# ican.net
KiCad netlist of a schematic drawn in EAGLE
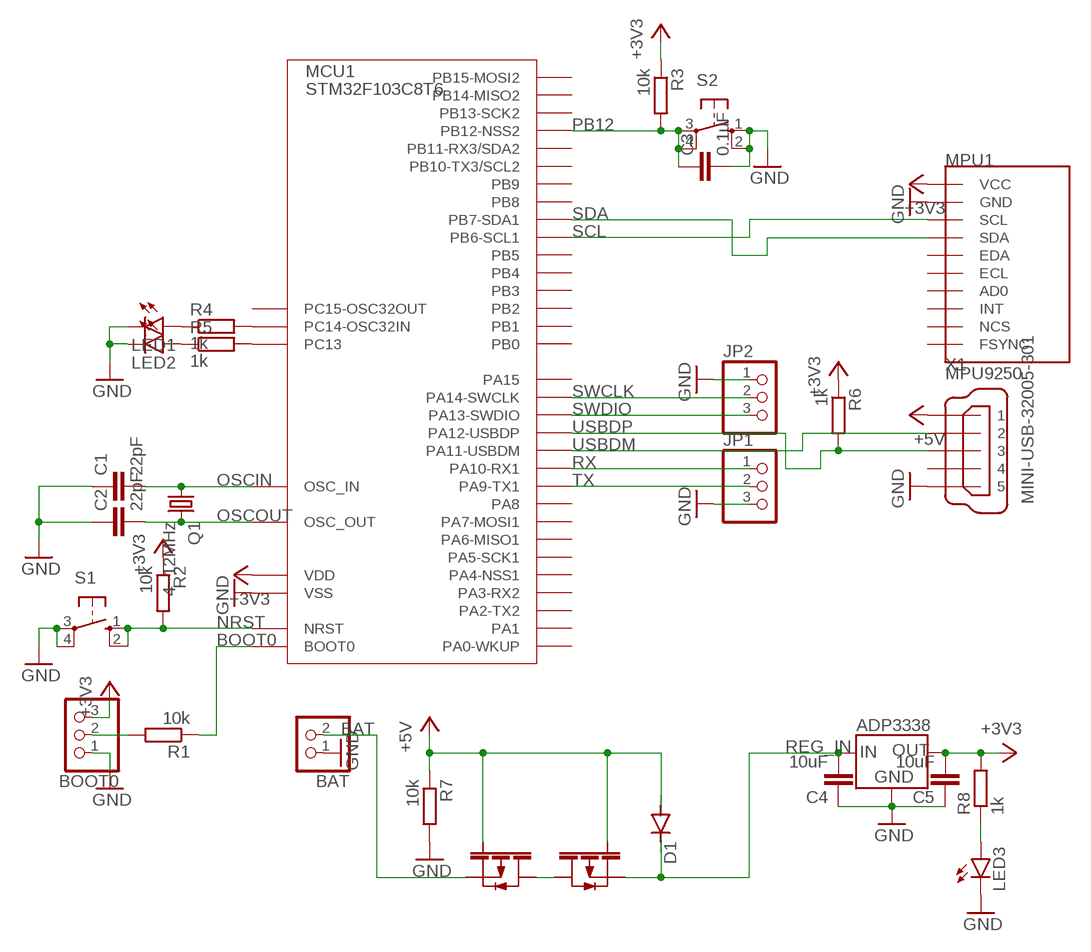
[diagram p0: schematic, sheet 1]

(export (version "E")
  (design (tool "Eeschema 10.0.6"))
  (components
    (comp (ref "BAT")
      (value "PINHD-1X2")
      (footprint "eagle-import:1X02")
      (libsource (lib "eagle-import") (part "PINHD-1X2"))
    )
    (comp (ref "BOOT0")
      (value "PINHD-1X3")
      (footprint "eagle-import:1X03")
      (libsource (lib "eagle-import") (part "PINHD-1X3"))
    )
    (comp (ref "C1")
      (value "22pF")
      (footprint "eagle-import:C2012")
      (libsource (lib "eagle-import") (part "C-EUC2012"))
    )
    (comp (ref "C2")
      (value "22pF")
      (footprint "eagle-import:C2012")
      (libsource (lib "eagle-import") (part "C-EUC2012"))
    )
    (comp (ref "C3")
      (value "0.1uF")
      (footprint "eagle-import:C2012")
      (libsource (lib "eagle-import") (part "C-EUC2012"))
    )
    (comp (ref "C4")
      (value "10uF")
      (footprint "eagle-import:C2012")
      (libsource (lib "eagle-import") (part "C-EUC2012"))
    )
    (comp (ref "C5")
      (value "10uF")
      (footprint "eagle-import:C2012")
      (libsource (lib "eagle-import") (part "C-EUC2012"))
    )
    (comp (ref "D1")
      (value "DIODE-SOD123")
      (footprint "eagle-import:SOD123")
      (libsource (lib "eagle-import") (part "DIODE-SOD123"))
    )
    (comp (ref "FET1")
      (value "PCH")
      (footprint "eagle-import:SOT-23")
      (libsource (lib "eagle-import") (part "PCH"))
    )
    (comp (ref "FET2")
      (value "PCH")
      (footprint "eagle-import:SOT-23")
      (libsource (lib "eagle-import") (part "PCH"))
    )
    (comp (ref "IC1")
      (value "ADP3338-3.3")
      (footprint "eagle-import:SOT-223")
      (libsource (lib "eagle-import") (part "ADP3338-3.3"))
    )
    (comp (ref "JP1")
      (value "PINHD-1X3")
      (footprint "eagle-import:1X03")
      (libsource (lib "eagle-import") (part "PINHD-1X3"))
    )
    (comp (ref "JP2")
      (value "PINHD-1X3")
      (footprint "eagle-import:1X03")
      (libsource (lib "eagle-import") (part "PINHD-1X3"))
    )
    (comp (ref "LED1")
      (value "LEDCHIPLED_1206")
      (footprint "eagle-import:CHIPLED_1206")
      (libsource (lib "eagle-import") (part "LEDCHIPLED_1206"))
    )
    (comp (ref "LED2")
      (value "LEDCHIPLED_1206")
      (footprint "eagle-import:CHIPLED_1206")
      (libsource (lib "eagle-import") (part "LEDCHIPLED_1206"))
    )
    (comp (ref "LED3")
      (value "LEDCHIPLED_1206")
      (footprint "eagle-import:CHIPLED_1206")
      (libsource (lib "eagle-import") (part "LEDCHIPLED_1206"))
    )
    (comp (ref "MCU1")
      (value "STM32F103C8T6")
      (footprint "eagle-import:LQFP48")
      (libsource (lib "eagle-import") (part "STM32F103C8T6"))
    )
    (comp (ref "MPU1")
      (value "MPU9250")
      (footprint "eagle-import:GY-9250")
      (libsource (lib "eagle-import") (part "MPU9250"))
    )
    (comp (ref "Q1")
      (value "4~12MHz")
      (footprint "eagle-import:HC49_S")
      (libsource (lib "eagle-import") (part "CRYSTALHC49S"))
    )
    (comp (ref "R1")
      (value "10k")
      (footprint "eagle-import:R2012")
      (libsource (lib "eagle-import") (part "R-EU_R2012"))
    )
    (comp (ref "R2")
      (value "10k")
      (footprint "eagle-import:R2012")
      (libsource (lib "eagle-import") (part "R-EU_R2012"))
    )
    (comp (ref "R3")
      (value "10k")
      (footprint "eagle-import:R2012")
      (libsource (lib "eagle-import") (part "R-EU_R2012"))
    )
    (comp (ref "R4")
      (value "1k")
      (footprint "eagle-import:R2012")
      (libsource (lib "eagle-import") (part "R-EU_R2012"))
    )
    (comp (ref "R5")
      (value "1k")
      (footprint "eagle-import:R2012")
      (libsource (lib "eagle-import") (part "R-EU_R2012"))
    )
    (comp (ref "R6")
      (value "1k")
      (footprint "eagle-import:R2012")
      (libsource (lib "eagle-import") (part "R-EU_R2012"))
    )
    (comp (ref "R7")
      (value "10k")
      (footprint "eagle-import:R2012")
      (libsource (lib "eagle-import") (part "R-EU_R2012"))
    )
    (comp (ref "R8")
      (value "1k")
      (footprint "eagle-import:R2012")
      (libsource (lib "eagle-import") (part "R-EU_R2012"))
    )
    (comp (ref "S1")
      (value "10-XX")
      (footprint "eagle-import:B3F-10XX")
      (fields (field (name "MPN") "B3F-1000"))
      (libsource (lib "eagle-import") (part "10-XX"))
    )
    (comp (ref "S2")
      (value "10-XX")
      (footprint "eagle-import:B3F-10XX")
      (fields (field (name "MPN") "B3F-1000"))
      (libsource (lib "eagle-import") (part "10-XX"))
    )
    (comp (ref "X1")
      (value "MINI-USB-32005-301")
      (footprint "eagle-import:32005-301")
      (libsource (lib "eagle-import") (part "MINI-USB-32005-301"))
    )
  )
  (nets
    (net (code "1") (name "+3V3") (class "Default")
      (node (ref "BOOT0") (pin "3") (pinfunction "3_3") (pintype "passive"))
      (node (ref "C5") (pin "2") (pinfunction "2_2") (pintype "passive"))
      (node (ref "IC1") (pin "1") (pinfunction "OUT_1") (pintype "output"))
      (node (ref "IC1") (pin "2") (pinfunction "OUT_2") (pintype "output"))
      (node (ref "MCU1") (pin "1") (pinfunction "VDD_1") (pintype "bidirectional"))
      (node (ref "MCU1") (pin "24") (pinfunction "VDD_24") (pintype "bidirectional"))
      (node (ref "MCU1") (pin "36") (pinfunction "VDD_36") (pintype "bidirectional"))
      (node (ref "MCU1") (pin "48") (pinfunction "VDD_48") (pintype "bidirectional"))
      (node (ref "MCU1") (pin "9") (pinfunction "VDD_9") (pintype "bidirectional"))
      (node (ref "MPU1") (pin "P1") (pinfunction "VCC_P1") (pintype "bidirectional"))
      (node (ref "R2") (pin "1") (pinfunction "1_1") (pintype "passive"))
      (node (ref "R3") (pin "1") (pinfunction "1_1") (pintype "passive"))
      (node (ref "R6") (pin "1") (pinfunction "1_1") (pintype "passive"))
      (node (ref "R8") (pin "2") (pinfunction "2_2") (pintype "passive"))
    )
    (net (code "2") (name "+5V") (class "Default")
      (node (ref "D1") (pin "A") (pinfunction "A_A") (pintype "passive"))
      (node (ref "FET1") (pin "P$1") (pinfunction "P$1_P$1") (pintype "bidirectional"))
      (node (ref "FET2") (pin "P$1") (pinfunction "P$1_P$1") (pintype "bidirectional"))
      (node (ref "R7") (pin "1") (pinfunction "1_1") (pintype "passive"))
      (node (ref "X1") (pin "1") (pinfunction "1_1") (pintype "passive"))
    )
    (net (code "3") (name "/BAT") (class "Default")
      (node (ref "BAT") (pin "2") (pinfunction "2_2") (pintype "passive"))
      (node (ref "FET1") (pin "P$2") (pinfunction "P$2_P$2") (pintype "bidirectional"))
    )
    (net (code "4") (name "/BOOT0") (class "Default")
      (node (ref "MCU1") (pin "44") (pinfunction "BOOT0_44") (pintype "bidirectional"))
      (node (ref "R1") (pin "1") (pinfunction "1_1") (pintype "passive"))
    )
    (net (code "5") (name "/NRST") (class "Default")
      (node (ref "MCU1") (pin "7") (pinfunction "NRST_7") (pintype "bidirectional"))
      (node (ref "R2") (pin "2") (pinfunction "2_2") (pintype "passive"))
      (node (ref "S1") (pin "1") (pinfunction "S_1") (pintype "passive"))
      (node (ref "S1") (pin "2") (pinfunction "S1_2") (pintype "passive"))
    )
    (net (code "6") (name "/OSCIN") (class "Default")
      (node (ref "C1") (pin "2") (pinfunction "2_2") (pintype "passive"))
      (node (ref "MCU1") (pin "5") (pinfunction "OSC_IN_5") (pintype "bidirectional"))
      (node (ref "Q1") (pin "1") (pinfunction "1_1") (pintype "passive"))
    )
    (net (code "7") (name "/OSCOUT") (class "Default")
      (node (ref "C2") (pin "2") (pinfunction "2_2") (pintype "passive"))
      (node (ref "MCU1") (pin "6") (pinfunction "OSC_OUT_6") (pintype "bidirectional"))
      (node (ref "Q1") (pin "2") (pinfunction "2_2") (pintype "passive"))
    )
    (net (code "8") (name "/PB12") (class "Default")
      (node (ref "C3") (pin "1") (pinfunction "1_1") (pintype "passive"))
      (node (ref "MCU1") (pin "25") (pinfunction "PB12-NSS2_25") (pintype "bidirectional"))
      (node (ref "R3") (pin "2") (pinfunction "2_2") (pintype "passive"))
      (node (ref "S2") (pin "3") (pinfunction "P_3") (pintype "passive"))
      (node (ref "S2") (pin "4") (pinfunction "P1_4") (pintype "passive"))
    )
    (net (code "9") (name "/REG_IN") (class "Default")
      (node (ref "C4") (pin "2") (pinfunction "2_2") (pintype "passive"))
      (node (ref "D1") (pin "C") (pinfunction "C_C") (pintype "passive"))
      (node (ref "FET2") (pin "P$2") (pinfunction "P$2_P$2") (pintype "bidirectional"))
      (node (ref "IC1") (pin "3") (pinfunction "IN_3") (pintype "input"))
    )
    (net (code "10") (name "/RX") (class "Default")
      (node (ref "JP1") (pin "1") (pinfunction "1_1") (pintype "passive"))
      (node (ref "MCU1") (pin "31") (pinfunction "PA10-RX1_31") (pintype "bidirectional"))
    )
    (net (code "11") (name "/SCL") (class "Default")
      (node (ref "MCU1") (pin "42") (pinfunction "PB6-SCL1_42") (pintype "bidirectional"))
      (node (ref "MPU1") (pin "P3") (pinfunction "SCL_P3") (pintype "bidirectional"))
    )
    (net (code "12") (name "/SDA") (class "Default")
      (node (ref "MCU1") (pin "43") (pinfunction "PB7-SDA1_43") (pintype "bidirectional"))
      (node (ref "MPU1") (pin "P4") (pinfunction "SDA_P4") (pintype "bidirectional"))
    )
    (net (code "13") (name "/SWCLK") (class "Default")
      (node (ref "JP2") (pin "2") (pinfunction "2_2") (pintype "passive"))
      (node (ref "MCU1") (pin "37") (pinfunction "PA14-SWCLK_37") (pintype "bidirectional"))
    )
    (net (code "14") (name "/SWDIO") (class "Default")
      (node (ref "JP2") (pin "3") (pinfunction "3_3") (pintype "passive"))
      (node (ref "MCU1") (pin "34") (pinfunction "PA13-SWDIO_34") (pintype "bidirectional"))
    )
    (net (code "15") (name "/TX") (class "Default")
      (node (ref "JP1") (pin "2") (pinfunction "2_2") (pintype "passive"))
      (node (ref "MCU1") (pin "30") (pinfunction "PA9-TX1_30") (pintype "bidirectional"))
    )
    (net (code "16") (name "/USBDM") (class "Default")
      (node (ref "MCU1") (pin "32") (pinfunction "PA11-USBDM_32") (pintype "bidirectional"))
      (node (ref "X1") (pin "2") (pinfunction "2_2") (pintype "passive"))
    )
    (net (code "17") (name "/USBDP") (class "Default")
      (node (ref "MCU1") (pin "33") (pinfunction "PA12-USBDP_33") (pintype "bidirectional"))
      (node (ref "R6") (pin "2") (pinfunction "2_2") (pintype "passive"))
      (node (ref "X1") (pin "3") (pinfunction "3_3") (pintype "passive"))
    )
    (net (code "18") (name "GND") (class "Default")
      (node (ref "BAT") (pin "1") (pinfunction "1_1") (pintype "passive"))
      (node (ref "BOOT0") (pin "1") (pinfunction "1_1") (pintype "passive"))
      (node (ref "C1") (pin "1") (pinfunction "1_1") (pintype "passive"))
      (node (ref "C2") (pin "1") (pinfunction "1_1") (pintype "passive"))
      (node (ref "C3") (pin "2") (pinfunction "2_2") (pintype "passive"))
      (node (ref "C4") (pin "1") (pinfunction "1_1") (pintype "passive"))
      (node (ref "C5") (pin "1") (pinfunction "1_1") (pintype "passive"))
      (node (ref "IC1") (pin "4") (pinfunction "GND_4") (pintype "bidirectional"))
      (node (ref "JP1") (pin "3") (pinfunction "3_3") (pintype "passive"))
      (node (ref "JP2") (pin "1") (pinfunction "1_1") (pintype "passive"))
      (node (ref "LED1") (pin "C") (pinfunction "C_C") (pintype "passive"))
      (node (ref "LED2") (pin "C") (pinfunction "C_C") (pintype "passive"))
      (node (ref "LED3") (pin "C") (pinfunction "C_C") (pintype "passive"))
      (node (ref "MCU1") (pin "23") (pinfunction "VSS_23") (pintype "bidirectional"))
      (node (ref "MCU1") (pin "35") (pinfunction "VSS_35") (pintype "bidirectional"))
      (node (ref "MCU1") (pin "47") (pinfunction "VSS_47") (pintype "bidirectional"))
      (node (ref "MCU1") (pin "8") (pinfunction "VSS_8") (pintype "bidirectional"))
      (node (ref "MPU1") (pin "P2") (pinfunction "GND_P2") (pintype "bidirectional"))
      (node (ref "R7") (pin "2") (pinfunction "2_2") (pintype "passive"))
      (node (ref "S1") (pin "3") (pinfunction "P_3") (pintype "passive"))
      (node (ref "S1") (pin "4") (pinfunction "P1_4") (pintype "passive"))
      (node (ref "S2") (pin "1") (pinfunction "S_1") (pintype "passive"))
      (node (ref "S2") (pin "2") (pinfunction "S1_2") (pintype "passive"))
      (node (ref "X1") (pin "5") (pinfunction "5_5") (pintype "passive"))
    )
    (net (code "19") (name "Net-(BOOT0-Pad2)") (class "Default")
      (node (ref "BOOT0") (pin "2") (pinfunction "2_2") (pintype "passive"))
      (node (ref "R1") (pin "2") (pinfunction "2_2") (pintype "passive"))
    )
    (net (code "20") (name "Net-(FET1-PadP$3)") (class "Default")
      (node (ref "FET1") (pin "P$3") (pinfunction "P$3_P$3") (pintype "bidirectional"))
      (node (ref "FET2") (pin "P$3") (pinfunction "P$3_P$3") (pintype "bidirectional"))
    )
    (net (code "21") (name "Net-(LED1-PadA)") (class "Default")
      (node (ref "LED1") (pin "A") (pinfunction "A_A") (pintype "passive"))
      (node (ref "R4") (pin "1") (pinfunction "1_1") (pintype "passive"))
    )
    (net (code "22") (name "Net-(LED2-PadA)") (class "Default")
      (node (ref "LED2") (pin "A") (pinfunction "A_A") (pintype "passive"))
      (node (ref "R5") (pin "1") (pinfunction "1_1") (pintype "passive"))
    )
    (net (code "23") (name "Net-(LED3-PadA)") (class "Default")
      (node (ref "LED3") (pin "A") (pinfunction "A_A") (pintype "passive"))
      (node (ref "R8") (pin "1") (pinfunction "1_1") (pintype "passive"))
    )
    (net (code "24") (name "Net-(MCU1-PC13)") (class "Default")
      (node (ref "MCU1") (pin "2") (pinfunction "PC13_2") (pintype "bidirectional"))
      (node (ref "R5") (pin "2") (pinfunction "2_2") (pintype "passive"))
    )
    (net (code "25") (name "Net-(MCU1-PC14-OSC32IN)") (class "Default")
      (node (ref "MCU1") (pin "3") (pinfunction "PC14-OSC32IN_3") (pintype "bidirectional"))
      (node (ref "R4") (pin "2") (pinfunction "2_2") (pintype "passive"))
    )
    (net (code "26") (name "unconnected-(MCU1-PA0-WKUP-Pad10)") (class "Default")
      (node (ref "MCU1") (pin "10") (pinfunction "PA0-WKUP_10") (pintype "bidirectional"))
    )
    (net (code "27") (name "unconnected-(MCU1-PA1-Pad11)") (class "Default")
      (node (ref "MCU1") (pin "11") (pinfunction "PA1_11") (pintype "bidirectional"))
    )
    (net (code "28") (name "unconnected-(MCU1-PA2-TX2-Pad12)") (class "Default")
      (node (ref "MCU1") (pin "12") (pinfunction "PA2-TX2_12") (pintype "bidirectional"))
    )
    (net (code "29") (name "unconnected-(MCU1-PA3-RX2-Pad13)") (class "Default")
      (node (ref "MCU1") (pin "13") (pinfunction "PA3-RX2_13") (pintype "bidirectional"))
    )
    (net (code "30") (name "unconnected-(MCU1-PA4-NSS1-Pad14)") (class "Default")
      (node (ref "MCU1") (pin "14") (pinfunction "PA4-NSS1_14") (pintype "bidirectional"))
    )
    (net (code "31") (name "unconnected-(MCU1-PA5-SCK1-Pad15)") (class "Default")
      (node (ref "MCU1") (pin "15") (pinfunction "PA5-SCK1_15") (pintype "bidirectional"))
    )
    (net (code "32") (name "unconnected-(MCU1-PA6-MISO1-Pad16)") (class "Default")
      (node (ref "MCU1") (pin "16") (pinfunction "PA6-MISO1_16") (pintype "bidirectional"))
    )
    (net (code "33") (name "unconnected-(MCU1-PA7-MOSI1-Pad17)") (class "Default")
      (node (ref "MCU1") (pin "17") (pinfunction "PA7-MOSI1_17") (pintype "bidirectional"))
    )
    (net (code "34") (name "unconnected-(MCU1-PA8-Pad29)") (class "Default")
      (node (ref "MCU1") (pin "29") (pinfunction "PA8_29") (pintype "bidirectional"))
    )
    (net (code "35") (name "unconnected-(MCU1-PA15-Pad38)") (class "Default")
      (node (ref "MCU1") (pin "38") (pinfunction "PA15_38") (pintype "bidirectional"))
    )
    (net (code "36") (name "unconnected-(MCU1-PB0-Pad18)") (class "Default")
      (node (ref "MCU1") (pin "18") (pinfunction "PB0_18") (pintype "bidirectional"))
    )
    (net (code "37") (name "unconnected-(MCU1-PB1-Pad19)") (class "Default")
      (node (ref "MCU1") (pin "19") (pinfunction "PB1_19") (pintype "bidirectional"))
    )
    (net (code "38") (name "unconnected-(MCU1-PB2-Pad20)") (class "Default")
      (node (ref "MCU1") (pin "20") (pinfunction "PB2_20") (pintype "bidirectional"))
    )
    (net (code "39") (name "unconnected-(MCU1-PB3-Pad39)") (class "Default")
      (node (ref "MCU1") (pin "39") (pinfunction "PB3_39") (pintype "bidirectional"))
    )
    (net (code "40") (name "unconnected-(MCU1-PB4-Pad40)") (class "Default")
      (node (ref "MCU1") (pin "40") (pinfunction "PB4_40") (pintype "bidirectional"))
    )
    (net (code "41") (name "unconnected-(MCU1-PB5-Pad41)") (class "Default")
      (node (ref "MCU1") (pin "41") (pinfunction "PB5_41") (pintype "bidirectional"))
    )
    (net (code "42") (name "unconnected-(MCU1-PB8-Pad45)") (class "Default")
      (node (ref "MCU1") (pin "45") (pinfunction "PB8_45") (pintype "bidirectional"))
    )
    (net (code "43") (name "unconnected-(MCU1-PB9-Pad46)") (class "Default")
      (node (ref "MCU1") (pin "46") (pinfunction "PB9_46") (pintype "bidirectional"))
    )
    (net (code "44") (name "unconnected-(MCU1-PB10-TX3{slash}SCL2-Pad21)") (class "Default")
      (node (ref "MCU1") (pin "21") (pinfunction "PB10-TX3/SCL2_21") (pintype "bidirectional"))
    )
    (net (code "45") (name "unconnected-(MCU1-PB11-RX3{slash}SDA2-Pad22)") (class "Default")
      (node (ref "MCU1") (pin "22") (pinfunction "PB11-RX3/SDA2_22") (pintype "bidirectional"))
    )
    (net (code "46") (name "unconnected-(MCU1-PB13-SCK2-Pad26)") (class "Default")
      (node (ref "MCU1") (pin "26") (pinfunction "PB13-SCK2_26") (pintype "bidirectional"))
    )
    (net (code "47") (name "unconnected-(MCU1-PB14-MISO2-Pad27)") (class "Default")
      (node (ref "MCU1") (pin "27") (pinfunction "PB14-MISO2_27") (pintype "bidirectional"))
    )
    (net (code "48") (name "unconnected-(MCU1-PB15-MOSI2-Pad28)") (class "Default")
      (node (ref "MCU1") (pin "28") (pinfunction "PB15-MOSI2_28") (pintype "bidirectional"))
    )
    (net (code "49") (name "unconnected-(MCU1-PC15-OSC32OUT-Pad4)") (class "Default")
      (node (ref "MCU1") (pin "4") (pinfunction "PC15-OSC32OUT_4") (pintype "bidirectional"))
    )
    (net (code "50") (name "unconnected-(MPU1-AD0-PadP7)") (class "Default")
      (node (ref "MPU1") (pin "P7") (pinfunction "AD0_P7") (pintype "bidirectional"))
    )
    (net (code "51") (name "unconnected-(MPU1-ECL-PadP6)") (class "Default")
      (node (ref "MPU1") (pin "P6") (pinfunction "ECL_P6") (pintype "bidirectional"))
    )
    (net (code "52") (name "unconnected-(MPU1-EDA-PadP5)") (class "Default")
      (node (ref "MPU1") (pin "P5") (pinfunction "EDA_P5") (pintype "bidirectional"))
    )
    (net (code "53") (name "unconnected-(MPU1-FSYNC-PadP10)") (class "Default")
      (node (ref "MPU1") (pin "P10") (pinfunction "FSYNC_P10") (pintype "bidirectional"))
    )
    (net (code "54") (name "unconnected-(MPU1-INT-PadP8)") (class "Default")
      (node (ref "MPU1") (pin "P8") (pinfunction "INT_P8") (pintype "bidirectional"))
    )
    (net (code "55") (name "unconnected-(MPU1-NCS-PadP9)") (class "Default")
      (node (ref "MPU1") (pin "P9") (pinfunction "NCS_P9") (pintype "bidirectional"))
    )
    (net (code "56") (name "unconnected-(X1-Pad4)") (class "Default")
      (node (ref "X1") (pin "4") (pinfunction "4_4") (pintype "passive"))
    )
  )
)
